# h-bridge-breakout.net
KiCad netlist of a schematic drawn in EAGLE
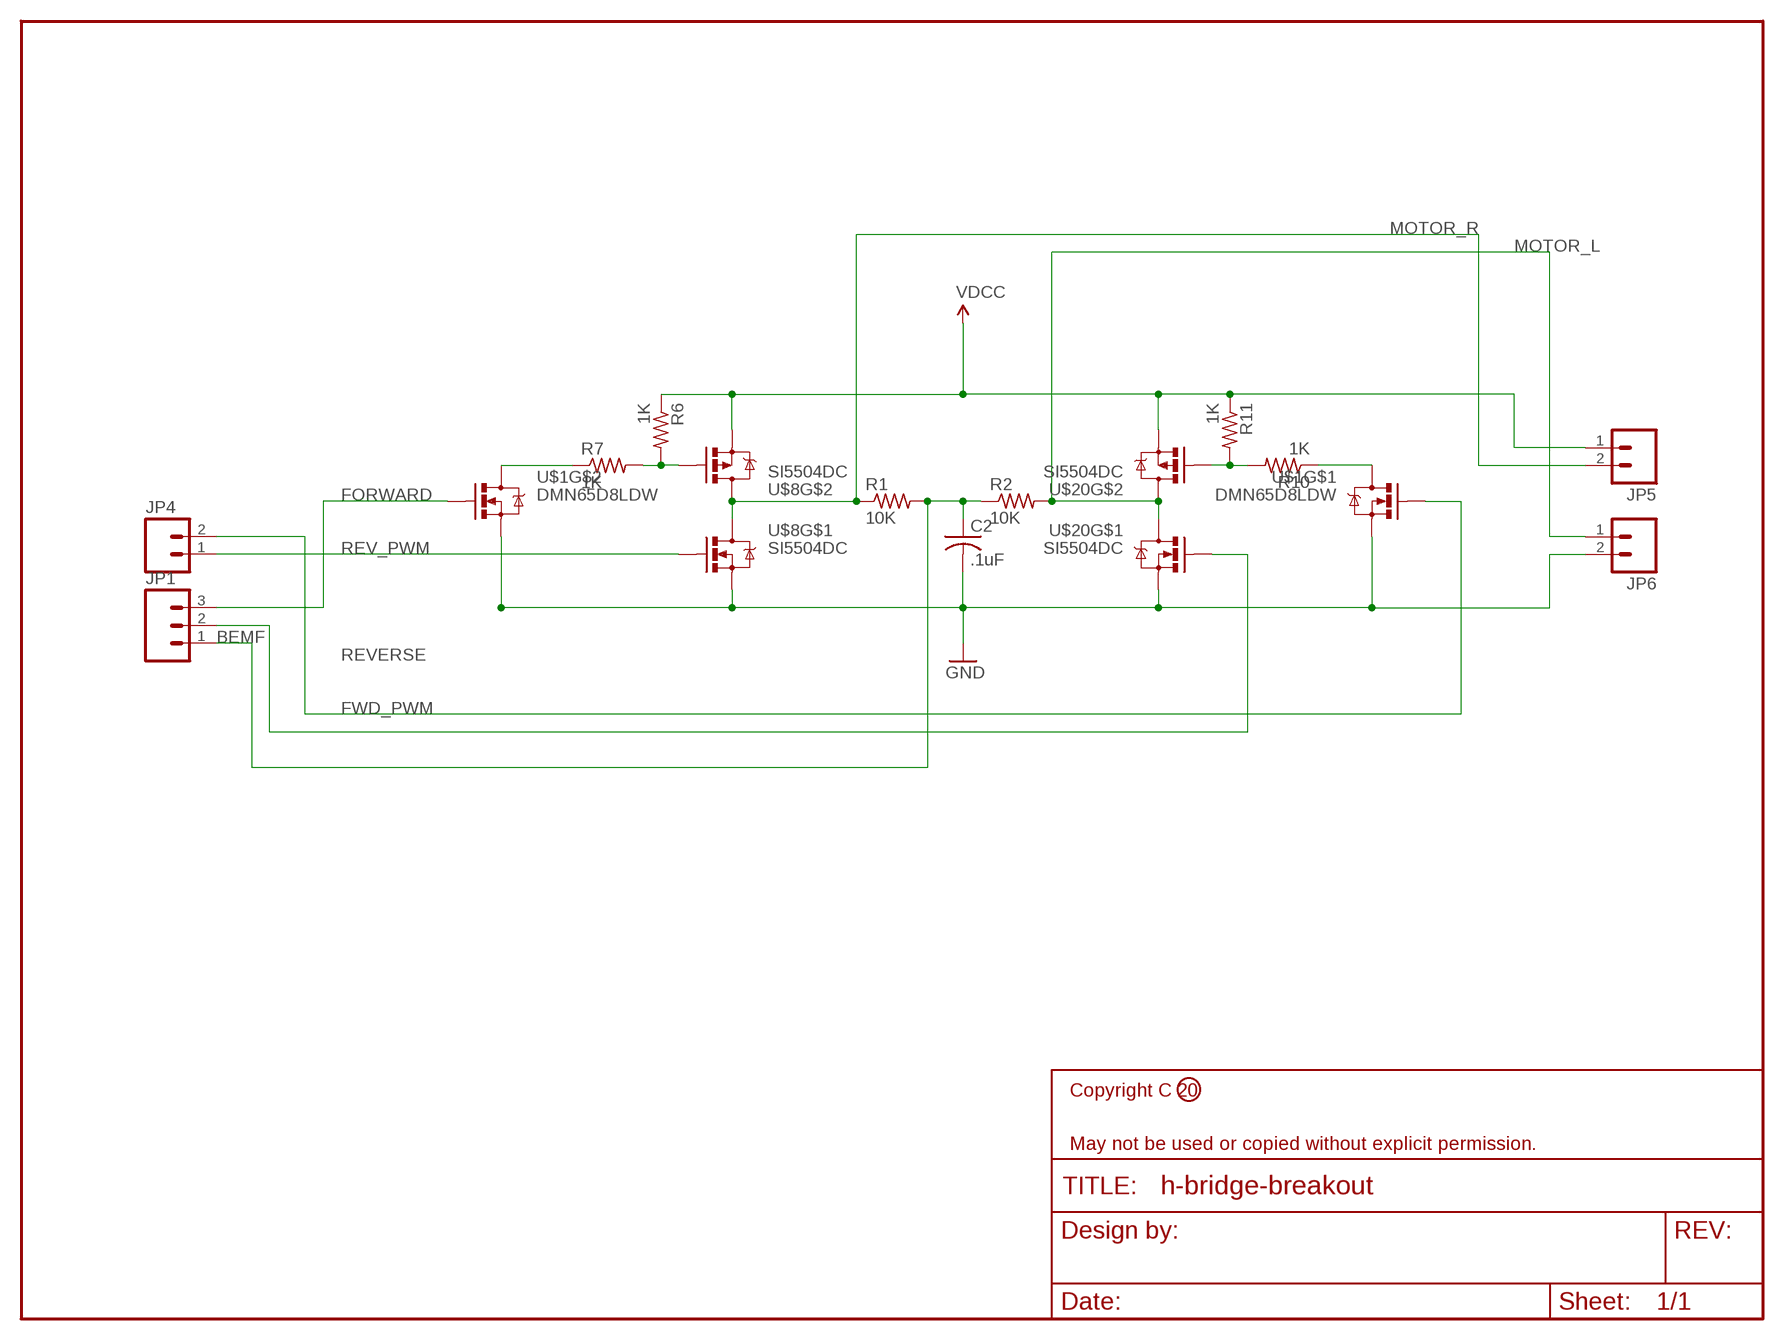
[diagram p0: schematic, sheet 1]

(export (version "E")
  (design (tool "Eeschema 10.0.6"))
  (components
    (comp (ref "C2")
      (value ".1uF")
      (footprint "eagle-import:C0402")
      (libsource (lib "eagle-import") (part "C-USC0402"))
    )
    (comp (ref "JP1")
      (value "M03SCREW")
      (footprint "eagle-import:SCREWTERMINAL-3.5MM-3")
      (libsource (lib "eagle-import") (part "M03SCREW"))
    )
    (comp (ref "JP4")
      (value "M023.5MM")
      (footprint "eagle-import:SCREWTERMINAL-3.5MM-2")
      (libsource (lib "eagle-import") (part "M023.5MM"))
    )
    (comp (ref "JP5")
      (value "M023.5MM")
      (footprint "eagle-import:SCREWTERMINAL-3.5MM-2")
      (libsource (lib "eagle-import") (part "M023.5MM"))
    )
    (comp (ref "JP6")
      (value "M023.5MM")
      (footprint "eagle-import:SCREWTERMINAL-3.5MM-2")
      (libsource (lib "eagle-import") (part "M023.5MM"))
    )
    (comp (ref "R1")
      (value "10K")
      (footprint "eagle-import:R0603")
      (libsource (lib "eagle-import") (part "R-US_R0603"))
    )
    (comp (ref "R2")
      (value "10K")
      (footprint "eagle-import:R0603")
      (libsource (lib "eagle-import") (part "R-US_R0603"))
    )
    (comp (ref "R6")
      (value "1K")
      (footprint "eagle-import:R0603")
      (libsource (lib "eagle-import") (part "R-US_R0603"))
    )
    (comp (ref "R7")
      (value "1K")
      (footprint "eagle-import:R0603")
      (libsource (lib "eagle-import") (part "R-US_R0603"))
    )
    (comp (ref "R10")
      (value "1K")
      (footprint "eagle-import:R0603")
      (libsource (lib "eagle-import") (part "R-US_R0603"))
    )
    (comp (ref "R11")
      (value "1K")
      (footprint "eagle-import:R0603")
      (libsource (lib "eagle-import") (part "R-US_R0603"))
    )
    (comp (ref "U$1")
      (value "DMN65D8LDW")
      (footprint "eagle-import:SOT363")
      (libsource (lib "eagle-import") (part "DMN65D8LDW"))
    )
    (comp (ref "U$8")
      (value "SI5504DC")
      (footprint "eagle-import:1206-8")
      (libsource (lib "eagle-import") (part "SI5504DC"))
    )
    (comp (ref "U$20")
      (value "SI5504DC")
      (footprint "eagle-import:1206-8")
      (libsource (lib "eagle-import") (part "SI5504DC"))
    )
  )
  (nets
    (net (code "1") (name "/BEMF") (class "Default")
      (node (ref "C2") (pin "1") (pinfunction "1_1") (pintype "passive"))
      (node (ref "JP1") (pin "1") (pinfunction "1_1") (pintype "passive"))
      (node (ref "R1") (pin "2") (pinfunction "2_2") (pintype "passive"))
      (node (ref "R2") (pin "1") (pinfunction "1_1") (pintype "passive"))
    )
    (net (code "2") (name "/FORWARD") (class "Default")
      (node (ref "JP1") (pin "3") (pinfunction "3_3") (pintype "passive"))
      (node (ref "U$1") (pin "P$5") (pinfunction "G_P$5") (pintype "passive"))
    )
    (net (code "3") (name "/FWD_PWM") (class "Default")
      (node (ref "JP1") (pin "2") (pinfunction "2_2") (pintype "passive"))
      (node (ref "U$20") (pin "P$2") (pinfunction "G_P$2") (pintype "passive"))
    )
    (net (code "4") (name "/MOTOR_L") (class "Default")
      (node (ref "JP6") (pin "1") (pinfunction "1_1") (pintype "passive"))
      (node (ref "R2") (pin "2") (pinfunction "2_2") (pintype "passive"))
      (node (ref "U$20") (pin "P$5") (pinfunction "D_P$5") (pintype "passive"))
      (node (ref "U$20") (pin "P$6") (pinfunction "D_P$6") (pintype "passive"))
      (node (ref "U$20") (pin "P$7") (pinfunction "D_P$7") (pintype "passive"))
      (node (ref "U$20") (pin "P$8") (pinfunction "D_P$8") (pintype "passive"))
    )
    (net (code "5") (name "/MOTOR_R") (class "Default")
      (node (ref "JP5") (pin "2") (pinfunction "2_2") (pintype "passive"))
      (node (ref "R1") (pin "1") (pinfunction "1_1") (pintype "passive"))
      (node (ref "U$8") (pin "P$5") (pinfunction "D_P$5") (pintype "passive"))
      (node (ref "U$8") (pin "P$6") (pinfunction "D_P$6") (pintype "passive"))
      (node (ref "U$8") (pin "P$7") (pinfunction "D_P$7") (pintype "passive"))
      (node (ref "U$8") (pin "P$8") (pinfunction "D_P$8") (pintype "passive"))
    )
    (net (code "6") (name "/REVERSE") (class "Default")
      (node (ref "JP4") (pin "2") (pinfunction "2_2") (pintype "passive"))
      (node (ref "U$1") (pin "P$2") (pinfunction "G_P$2") (pintype "passive"))
    )
    (net (code "7") (name "/REV_PWM") (class "Default")
      (node (ref "JP4") (pin "1") (pinfunction "1_1") (pintype "passive"))
      (node (ref "U$8") (pin "P$2") (pinfunction "G_P$2") (pintype "passive"))
    )
    (net (code "8") (name "GND") (class "Default")
      (node (ref "C2") (pin "2") (pinfunction "2_2") (pintype "passive"))
      (node (ref "JP6") (pin "2") (pinfunction "2_2") (pintype "passive"))
      (node (ref "U$1") (pin "P$3") (pinfunction "S_P$3") (pintype "passive"))
      (node (ref "U$1") (pin "P$6") (pinfunction "S_P$6") (pintype "passive"))
      (node (ref "U$20") (pin "P$1") (pinfunction "S_P$1") (pintype "passive"))
      (node (ref "U$8") (pin "P$1") (pinfunction "S_P$1") (pintype "passive"))
    )
    (net (code "9") (name "Net-(U$1A-D)") (class "Default")
      (node (ref "R10") (pin "1") (pinfunction "1_1") (pintype "passive"))
      (node (ref "U$1") (pin "P$4") (pinfunction "D_P$4") (pintype "passive"))
    )
    (net (code "10") (name "Net-(U$1B-D)") (class "Default")
      (node (ref "R7") (pin "1") (pinfunction "1_1") (pintype "passive"))
      (node (ref "U$1") (pin "P$1") (pinfunction "D_P$1") (pintype "passive"))
    )
    (net (code "11") (name "Net-(U$8B-G)") (class "Default")
      (node (ref "R6") (pin "2") (pinfunction "2_2") (pintype "passive"))
      (node (ref "R7") (pin "2") (pinfunction "2_2") (pintype "passive"))
      (node (ref "U$8") (pin "P$4") (pinfunction "G_P$4") (pintype "passive"))
    )
    (net (code "12") (name "Net-(U$20B-G)") (class "Default")
      (node (ref "R10") (pin "2") (pinfunction "2_2") (pintype "passive"))
      (node (ref "R11") (pin "2") (pinfunction "2_2") (pintype "passive"))
      (node (ref "U$20") (pin "P$4") (pinfunction "G_P$4") (pintype "passive"))
    )
    (net (code "13") (name "VDCC") (class "Default")
      (node (ref "JP5") (pin "1") (pinfunction "1_1") (pintype "passive"))
      (node (ref "R11") (pin "1") (pinfunction "1_1") (pintype "passive"))
      (node (ref "R6") (pin "1") (pinfunction "1_1") (pintype "passive"))
      (node (ref "U$20") (pin "P$3") (pinfunction "S_P$3") (pintype "passive"))
      (node (ref "U$8") (pin "P$3") (pinfunction "S_P$3") (pintype "passive"))
    )
  )
)
